# COMPONENT_BLOCKS_1.net
KiCad netlist of a schematic drawn in Altium Designer
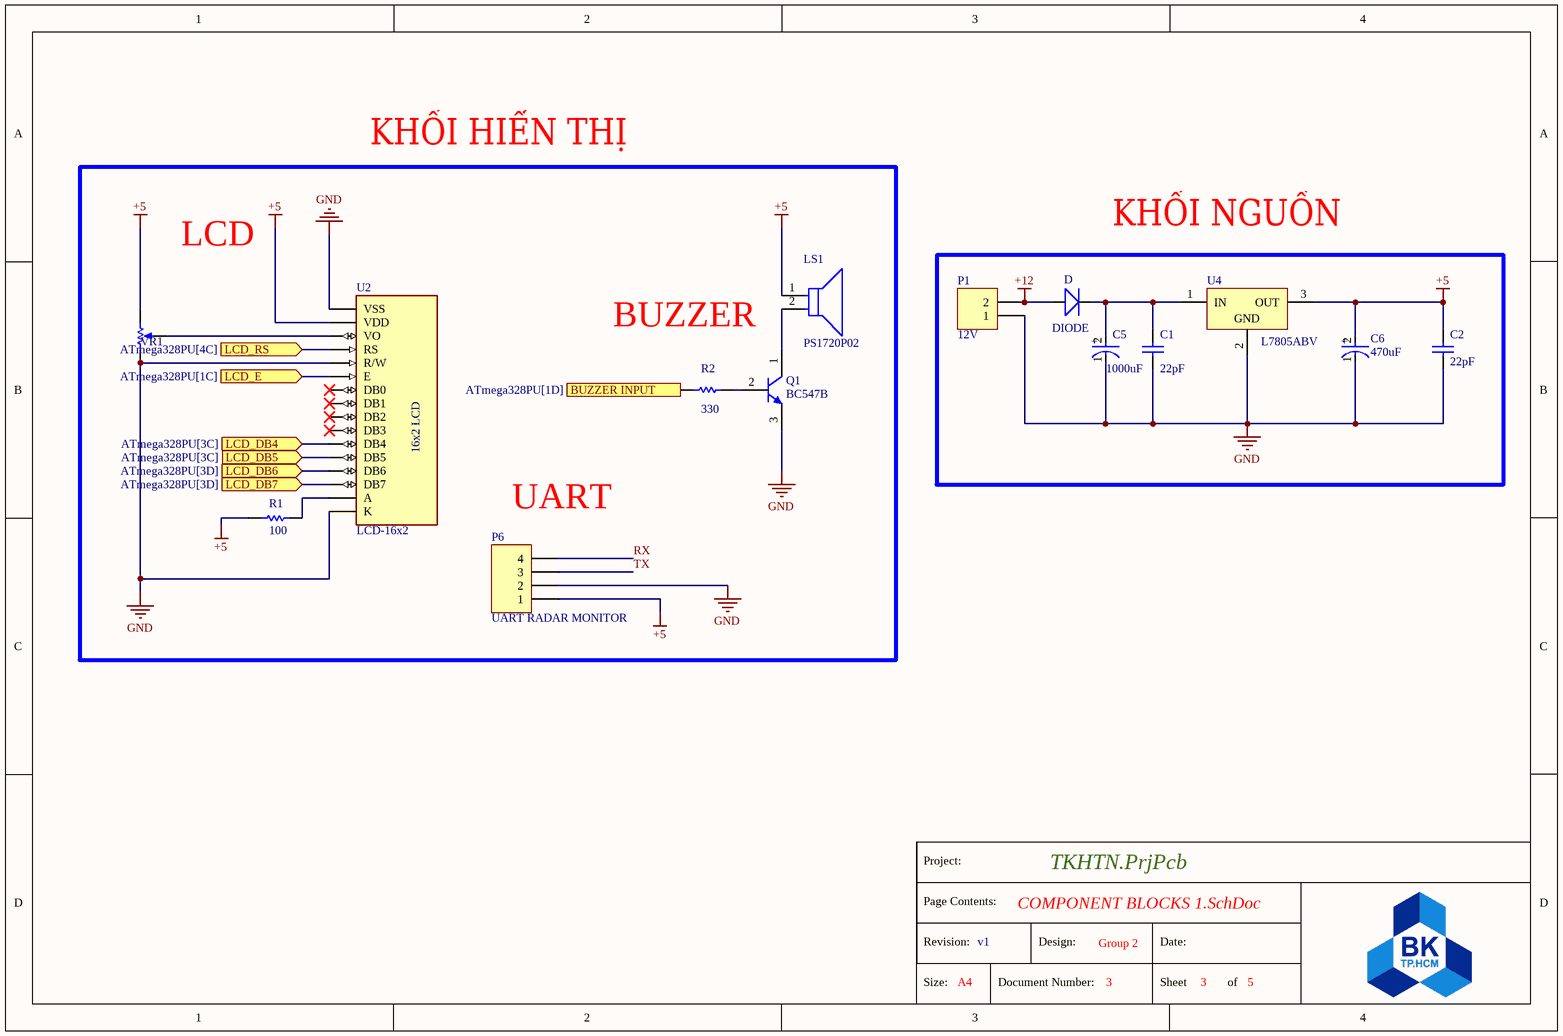
[diagram p0: COMPONENT BLOCKS 1.SchDoc]

(export (version "E")
  (design (tool "Eeschema 10.0.6"))
  (components
    (comp (ref "C1")
      (value "22pF")
      (footprint "RAD-0.3")
      (description "Capacitor")
      (fields (field (name "Comment") "Cap") (field (name "PUBLISHER") "Altium Limited"))
      (libsource (lib "Miscellaneous Devices") (part "Cap"))
    )
    (comp (ref "C2")
      (value "22pF")
      (footprint "RAD-0.3")
      (description "Capacitor")
      (fields (field (name "Comment") "Cap") (field (name "PUBLISHER") "Altium Limited"))
      (libsource (lib "Miscellaneous Devices") (part "Cap"))
    )
    (comp (ref "C5")
      (value "1000uF")
      (footprint "FP-SMR-P45-MFG")
      (description "CAP ALUM 270UF 20% 450V SNAP")
      (fields (field (name "TOLERANCE") "20%"))
      (libsource (lib "capacitor polarized") (part "CMP-33768-000007-1"))
    )
    (comp (ref "C6")
      (value "470uF")
      (footprint "FP-SMR-P45-MFG")
      (description "CAP ALUM 270UF 20% 450V SNAP")
      (fields (field (name "TOLERANCE") "20%"))
      (libsource (lib "capacitor polarized") (part "CMP-33768-000007-1"))
    )
    (comp (ref "D")
      (value "DIODE")
      (footprint "DO-41")
      (description "Diode Standard 50V 1A Through Hole DO-41")
      (fields (field (name "MF") "Comchip Technology") (field (name "MP") "1N4001-G"))
      (libsource (lib "SnapEDAsch") (part "DIP-DIODE-50V-1A(DO-41)"))
    )
    (comp (ref "LS1")
      (value "PS1720P02")
      (footprint "FP-PS1720P02-MFG")
      (description "AUDIO PIEZO TRANSDUCER 30V TH")
      (fields
        (field (name "OCTOPART") "https://octopart.com/ps1720p02-tdk-154429")
        (field (name "MANUFACTURER") "TDK Corporation")
      )
      (libsource (lib "piezo buzzer") (part "CMP-08413-000001-1"))
    )
    (comp (ref "P1")
      (value "12V")
      (footprint "HDR1X2")
      (description "Header, 2-Pin")
      (fields (field (name "PUBLISHER") "Altium Limited"))
      (libsource (lib "Miscellaneous Connectors") (part "Header 2"))
    )
    (comp (ref "P6")
      (value "UART RADAR MONITOR")
      (footprint "HDR1X4")
      (description "Header, 4-Pin")
      (fields (field (name "PUBLISHER") "Altium Limited"))
      (libsource (lib "Miscellaneous Connectors") (part "Header 4"))
    )
    (comp (ref "Q1")
      (value "BC547B")
      (footprint "ONSC-TO-92-3-29-11")
      (description "Amplifier Transistor, NPN Silicon, 3-Pin TO-92, Bulk Box")
      (fields (field (name "MANUFACTURER") "On Semiconductor"))
      (libsource (lib "npn bc547") (part "CMP-1048-01467-1"))
    )
    (comp (ref "R1")
      (value "100")
      (footprint "AXIAL-0.3")
      (description "Resistor")
      (fields (field (name "Comment") "Res1") (field (name "PUBLISHER") "Altium Limited"))
      (libsource (lib "Miscellaneous Devices") (part "Res1"))
    )
    (comp (ref "R2")
      (value "330")
      (footprint "AXIAL-0.3")
      (description "Resistor")
      (fields (field (name "Comment") "Res1") (field (name "PUBLISHER") "Altium Limited"))
      (libsource (lib "Miscellaneous Devices") (part "Res1"))
    )
    (comp (ref "U2")
      (value "LCD-16x2")
      (footprint "MODULE_LCD-16X2")
      (description "Display Development Tools 20x4 Black on Green Char LCD w Backlight")
      (fields (field (name "MF") "Gravitech") (field (name "MP") "LCD-16X2"))
      (libsource (lib "LCD-16X2") (part "LCD-16X2"))
    )
    (comp (ref "U4")
      (value "L7805ABV")
      (footprint "TO220")
      (description "Positive Voltage Regulator, 5V, 3-Pin TO-220")
      (libsource (lib "Voltage source 5v") (part "CMP-0244-00485-1"))
    )
    (comp (ref "VR1")
      (value "RPot")
      (footprint "VR5")
      (description "Potentiometer")
      (fields (field (name "PUBLISHER") "Altium Limited"))
      (libsource (lib "Miscellaneous Devices") (part "RPot"))
    )
  )
  (nets
    (net (code "1") (name "+5") (class "Default")
      (node (ref "C2") (pin "2") (pinfunction "2_2") (pintype "passive"))
      (node (ref "C6") (pin "2") (pinfunction "A_2") (pintype "passive"))
      (node (ref "LS1") (pin "1") (pinfunction "1_1") (pintype "passive"))
      (node (ref "P6") (pin "1") (pinfunction "1_1") (pintype "passive"))
      (node (ref "R1") (pin "1") (pinfunction "1_1") (pintype "passive"))
      (node (ref "U2") (pin "2") (pinfunction "VDD_2") (pintype "power_in"))
      (node (ref "U4") (pin "3") (pinfunction "OUT_3") (pintype "power_in"))
      (node (ref "VR1") (pin "2") (pinfunction "BOT_2") (pintype "passive"))
    )
    (net (code "2") (name "+12") (class "Default")
      (node (ref "D") (pin "1") (pinfunction "POS_1") (pintype "passive"))
      (node (ref "P1") (pin "2") (pinfunction "2_2") (pintype "passive"))
    )
    (net (code "3") (name "/BUZZER INPUT") (class "Default")
      (node (ref "R2") (pin "1") (pinfunction "1_1") (pintype "passive"))
    )
    (net (code "4") (name "/LCD_DB4") (class "Default")
      (node (ref "U2") (pin "11") (pinfunction "DB4_11") (pintype "bidirectional"))
    )
    (net (code "5") (name "/LCD_DB5") (class "Default")
      (node (ref "U2") (pin "12") (pinfunction "DB5_12") (pintype "bidirectional"))
    )
    (net (code "6") (name "/LCD_DB6") (class "Default")
      (node (ref "U2") (pin "13") (pinfunction "DB6_13") (pintype "bidirectional"))
    )
    (net (code "7") (name "/LCD_DB7") (class "Default")
      (node (ref "U2") (pin "14") (pinfunction "DB7_14") (pintype "bidirectional"))
    )
    (net (code "8") (name "/LCD_E") (class "Default")
      (node (ref "U2") (pin "6") (pinfunction "E_6") (pintype "input"))
    )
    (net (code "9") (name "/LCD_RS") (class "Default")
      (node (ref "U2") (pin "4") (pinfunction "RS_4") (pintype "input"))
    )
    (net (code "10") (name "/RX") (class "Default")
      (node (ref "P6") (pin "4") (pinfunction "4_4") (pintype "passive"))
    )
    (net (code "11") (name "/TX") (class "Default")
      (node (ref "P6") (pin "3") (pinfunction "3_3") (pintype "passive"))
    )
    (net (code "12") (name "GND") (class "Default")
      (node (ref "C1") (pin "1") (pinfunction "1_1") (pintype "passive"))
      (node (ref "C2") (pin "1") (pinfunction "1_1") (pintype "passive"))
      (node (ref "C5") (pin "1") (pinfunction "C_1") (pintype "passive"))
      (node (ref "C6") (pin "1") (pinfunction "C_1") (pintype "passive"))
      (node (ref "P1") (pin "1") (pinfunction "1_1") (pintype "passive"))
      (node (ref "P6") (pin "2") (pinfunction "2_2") (pintype "passive"))
      (node (ref "Q1") (pin "3") (pinfunction "E_3") (pintype "passive"))
      (node (ref "U2") (pin "1") (pinfunction "VSS_1") (pintype "power_in"))
      (node (ref "U2") (pin "16") (pinfunction "K_16") (pintype "power_in"))
      (node (ref "U2") (pin "5") (pinfunction "R/W_5") (pintype "input"))
      (node (ref "U4") (pin "2") (pinfunction "GND_2") (pintype "power_in"))
      (node (ref "VR1") (pin "1") (pinfunction "TOP_1") (pintype "passive"))
    )
    (net (code "13") (name "Net-(C5-A)") (class "Default")
      (node (ref "C1") (pin "2") (pinfunction "2_2") (pintype "passive"))
      (node (ref "C5") (pin "2") (pinfunction "A_2") (pintype "passive"))
      (node (ref "D") (pin "2") (pinfunction "NEG_2") (pintype "passive"))
      (node (ref "U4") (pin "1") (pinfunction "IN_1") (pintype "power_in"))
    )
    (net (code "14") (name "Net-(Q1-B)") (class "Default")
      (node (ref "Q1") (pin "2") (pinfunction "B_2") (pintype "passive"))
      (node (ref "R2") (pin "2") (pinfunction "2_2") (pintype "passive"))
    )
    (net (code "15") (name "Net-(Q1-C)") (class "Default")
      (node (ref "LS1") (pin "2") (pinfunction "2_2") (pintype "passive"))
      (node (ref "Q1") (pin "1") (pinfunction "C_1") (pintype "passive"))
    )
    (net (code "16") (name "Net-(U2-A)") (class "Default")
      (node (ref "R1") (pin "2") (pinfunction "2_2") (pintype "passive"))
      (node (ref "U2") (pin "15") (pinfunction "A_15") (pintype "power_in"))
    )
    (net (code "17") (name "Net-(U2-VO)") (class "Default")
      (node (ref "U2") (pin "3") (pinfunction "VO_3") (pintype "bidirectional"))
      (node (ref "VR1") (pin "3") (pinfunction "TAP_3") (pintype "passive"))
    )
    (net (code "18") (name "unconnected-(U2-DB0-Pad7)") (class "Default")
      (node (ref "U2") (pin "7") (pinfunction "DB0_7") (pintype "bidirectional+no_connect"))
    )
    (net (code "19") (name "unconnected-(U2-DB1-Pad8)") (class "Default")
      (node (ref "U2") (pin "8") (pinfunction "DB1_8") (pintype "bidirectional+no_connect"))
    )
    (net (code "20") (name "unconnected-(U2-DB2-Pad9)") (class "Default")
      (node (ref "U2") (pin "9") (pinfunction "DB2_9") (pintype "bidirectional+no_connect"))
    )
    (net (code "21") (name "unconnected-(U2-DB3-Pad10)") (class "Default")
      (node (ref "U2") (pin "10") (pinfunction "DB3_10") (pintype "bidirectional+no_connect"))
    )
  )
)
